# ui.net
KiCad netlist of a schematic drawn in Altium Designer
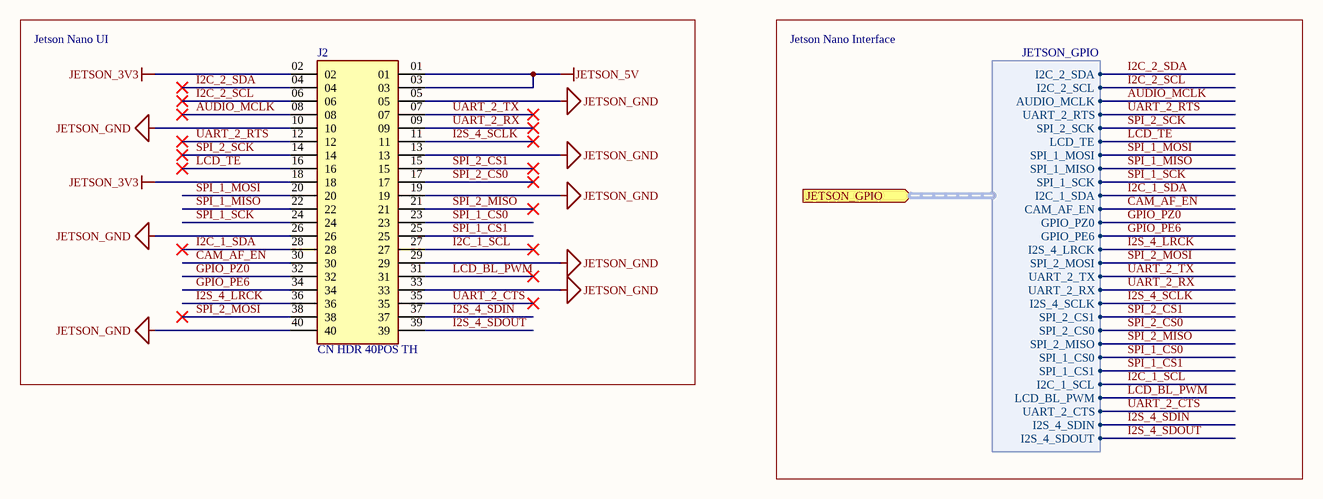
[diagram p0: ui.SchDoc]

(export (version "E")
  (design (tool "Eeschema 10.0.6"))
  (components
    (comp (ref "J2")
      (value "CN HDR 40POS TH")
      (footprint "SAMTEC_SSQ-120-22-G-D")
      (description "SSQ - Samtec 2.54mm Square Tail Dual Row Socket Strip 8.5mm Profile")
      (fields (field (name "MF") "Samtec") (field (name "MP") "SSQ-120-22-G-D"))
      (libsource (lib "AltiumLibraries") (part "CN HDR 40POS TH"))
    )
  )
  (nets
    (net (code "2") (name "/AUDIO_MCLK") (class "Default")
      (node (ref "J2") (pin "08") (pinfunction "08_08") (pintype "passive"))
    )
    (net (code "3") (name "/CAM_AF_EN") (class "Default")
      (node (ref "J2") (pin "30") (pinfunction "30_30") (pintype "passive"))
    )
    (net (code "4") (name "/GPIO_PE6") (class "Default")
      (node (ref "J2") (pin "34") (pinfunction "34_34") (pintype "passive"))
    )
    (net (code "5") (name "/GPIO_PZ0") (class "Default")
      (node (ref "J2") (pin "32") (pinfunction "32_32") (pintype "passive"))
    )
    (net (code "6") (name "/I2C_1_SCL") (class "Default")
      (node (ref "J2") (pin "27") (pinfunction "27_27") (pintype "passive+no_connect"))
    )
    (net (code "7") (name "/I2C_1_SDA") (class "Default")
      (node (ref "J2") (pin "28") (pinfunction "28_28") (pintype "passive+no_connect"))
    )
    (net (code "8") (name "/I2C_2_SCL") (class "Default")
      (node (ref "J2") (pin "06") (pinfunction "06_06") (pintype "passive"))
    )
    (net (code "9") (name "/I2C_2_SDA") (class "Default")
      (node (ref "J2") (pin "04") (pinfunction "04_04") (pintype "passive"))
    )
    (net (code "10") (name "/I2S_4_LRCK") (class "Default")
      (node (ref "J2") (pin "36") (pinfunction "36_36") (pintype "passive"))
    )
    (net (code "11") (name "/I2S_4_SCLK") (class "Default")
      (node (ref "J2") (pin "11") (pinfunction "11_11") (pintype "passive+no_connect"))
    )
    (net (code "12") (name "/I2S_4_SDIN") (class "Default")
      (node (ref "J2") (pin "37") (pinfunction "37_37") (pintype "passive"))
    )
    (net (code "13") (name "/I2S_4_SDOUT") (class "Default")
      (node (ref "J2") (pin "39") (pinfunction "39_39") (pintype "passive"))
    )
    (net (code "14") (name "/LCD_BL_PWM") (class "Default")
      (node (ref "J2") (pin "31") (pinfunction "31_31") (pintype "passive+no_connect"))
    )
    (net (code "15") (name "/LCD_TE") (class "Default")
      (node (ref "J2") (pin "16") (pinfunction "16_16") (pintype "passive"))
    )
    (net (code "16") (name "/SPI_1_CS0") (class "Default")
      (node (ref "J2") (pin "23") (pinfunction "23_23") (pintype "passive"))
    )
    (net (code "17") (name "/SPI_1_CS1") (class "Default")
      (node (ref "J2") (pin "25") (pinfunction "25_25") (pintype "passive"))
    )
    (net (code "18") (name "/SPI_1_MISO") (class "Default")
      (node (ref "J2") (pin "22") (pinfunction "22_22") (pintype "passive"))
    )
    (net (code "19") (name "/SPI_1_MOSI") (class "Default")
      (node (ref "J2") (pin "20") (pinfunction "20_20") (pintype "passive"))
    )
    (net (code "20") (name "/SPI_1_SCK") (class "Default")
      (node (ref "J2") (pin "24") (pinfunction "24_24") (pintype "passive"))
    )
    (net (code "21") (name "/SPI_2_CS0") (class "Default")
      (node (ref "J2") (pin "17") (pinfunction "17_17") (pintype "passive+no_connect"))
    )
    (net (code "22") (name "/SPI_2_CS1") (class "Default")
      (node (ref "J2") (pin "15") (pinfunction "15_15") (pintype "passive+no_connect"))
    )
    (net (code "23") (name "/SPI_2_MISO") (class "Default")
      (node (ref "J2") (pin "21") (pinfunction "21_21") (pintype "passive+no_connect"))
    )
    (net (code "24") (name "/SPI_2_MOSI") (class "Default")
      (node (ref "J2") (pin "38") (pinfunction "38_38") (pintype "passive+no_connect"))
    )
    (net (code "25") (name "/SPI_2_SCK") (class "Default")
      (node (ref "J2") (pin "14") (pinfunction "14_14") (pintype "passive"))
    )
    (net (code "26") (name "/UART_2_CTS") (class "Default")
      (node (ref "J2") (pin "35") (pinfunction "35_35") (pintype "passive"))
    )
    (net (code "27") (name "/UART_2_RTS") (class "Default")
      (node (ref "J2") (pin "12") (pinfunction "12_12") (pintype "passive"))
    )
    (net (code "28") (name "/UART_2_RX") (class "Default")
      (node (ref "J2") (pin "09") (pinfunction "09_09") (pintype "passive+no_connect"))
    )
    (net (code "29") (name "/UART_2_TX") (class "Default")
      (node (ref "J2") (pin "07") (pinfunction "07_07") (pintype "passive+no_connect"))
    )
    (net (code "31") (name "JETSON_3V3") (class "Default")
      (node (ref "J2") (pin "02") (pinfunction "02_02") (pintype "passive"))
      (node (ref "J2") (pin "18") (pinfunction "18_18") (pintype "passive"))
    )
    (net (code "32") (name "JETSON_5V") (class "Default")
      (node (ref "J2") (pin "01") (pinfunction "01_01") (pintype "passive"))
      (node (ref "J2") (pin "03") (pinfunction "03_03") (pintype "passive"))
    )
    (net (code "33") (name "JETSON_GND") (class "Default")
      (node (ref "J2") (pin "05") (pinfunction "05_05") (pintype "passive"))
      (node (ref "J2") (pin "10") (pinfunction "10_10") (pintype "passive"))
      (node (ref "J2") (pin "13") (pinfunction "13_13") (pintype "passive"))
      (node (ref "J2") (pin "19") (pinfunction "19_19") (pintype "passive"))
      (node (ref "J2") (pin "26") (pinfunction "26_26") (pintype "passive"))
      (node (ref "J2") (pin "29") (pinfunction "29_29") (pintype "passive"))
      (node (ref "J2") (pin "33") (pinfunction "33_33") (pintype "passive"))
      (node (ref "J2") (pin "40") (pinfunction "40_40") (pintype "passive"))
    )
  )
)
